# DasAltimeter_V0_41.net
KiCad netlist of a schematic drawn in EAGLE
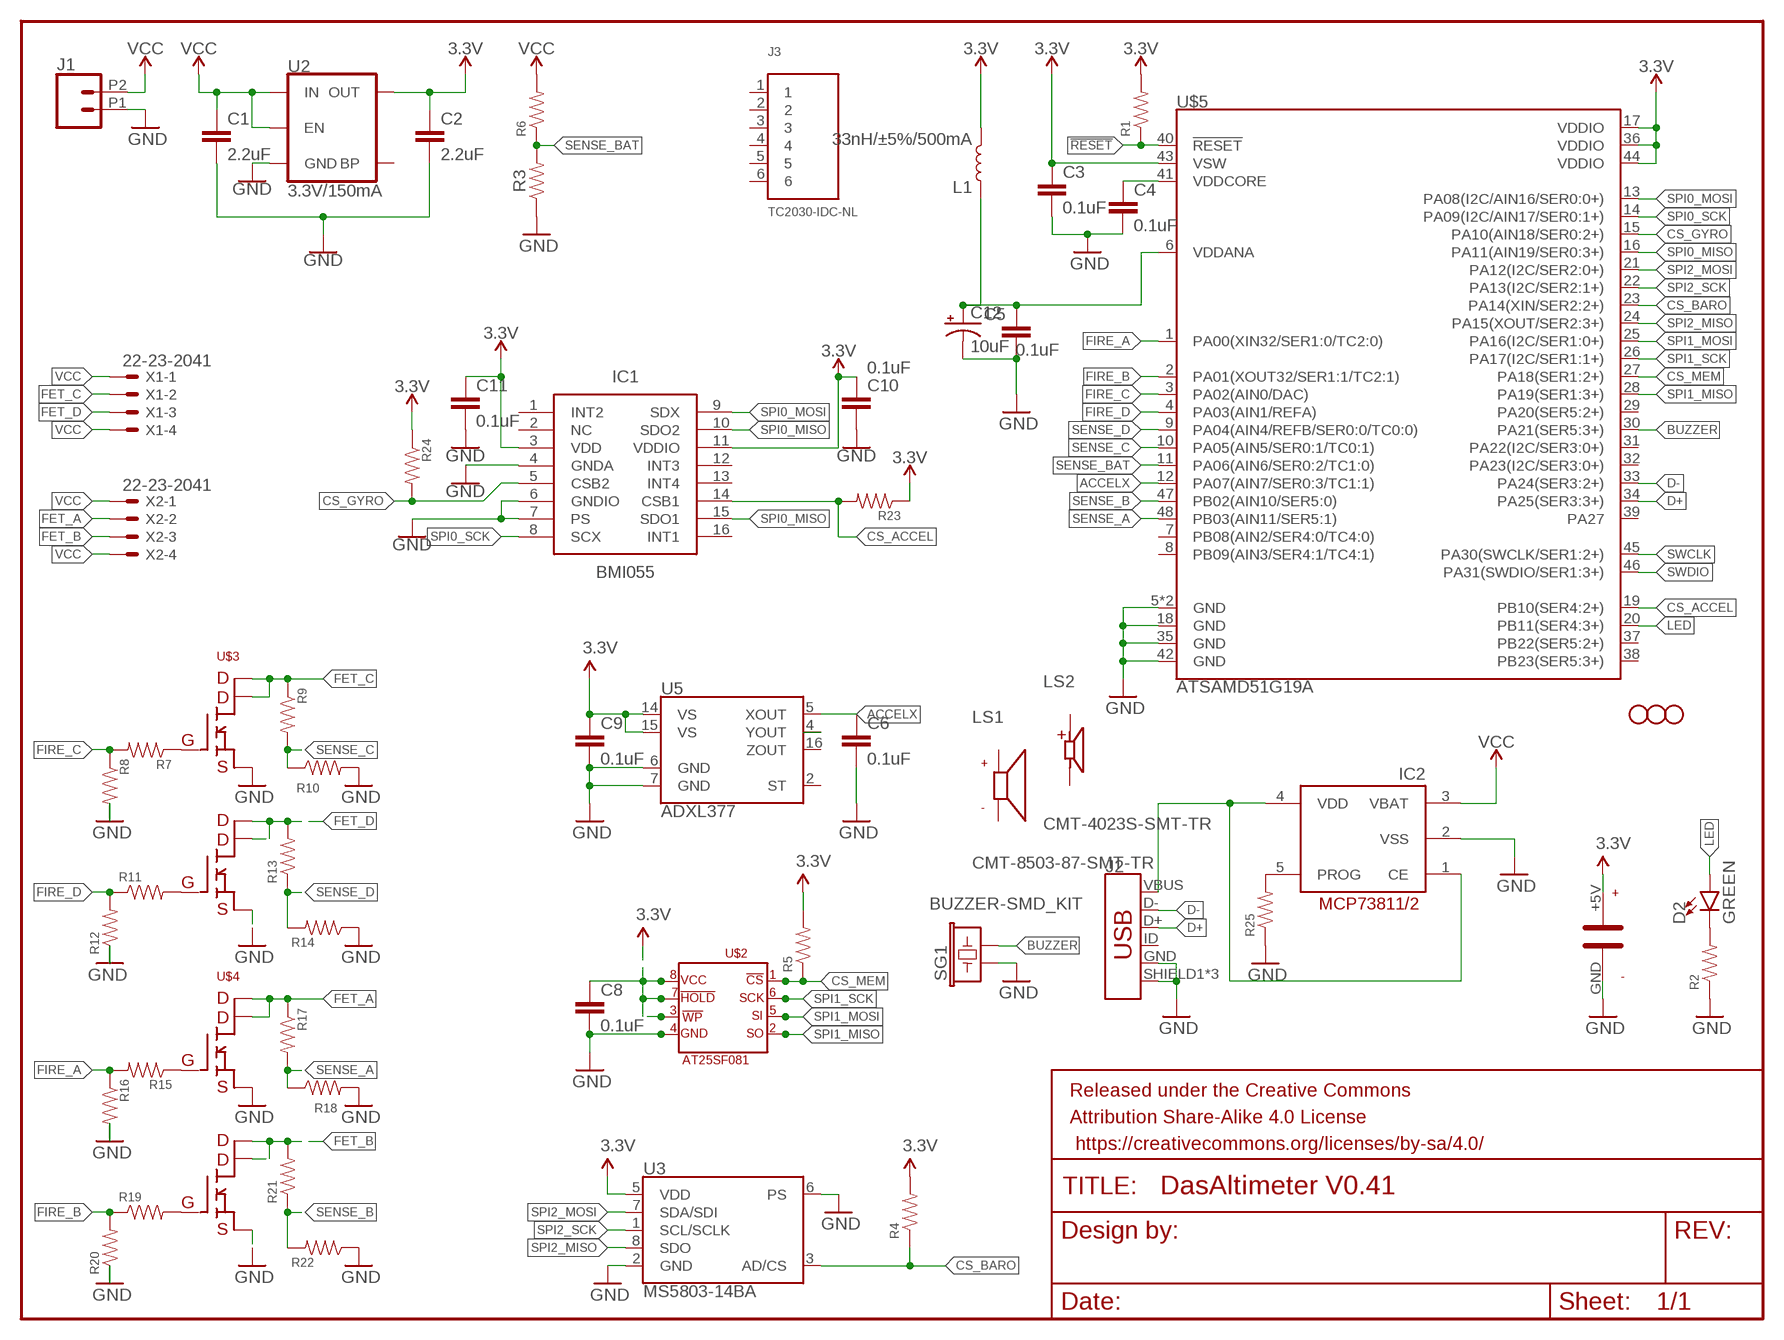
[diagram p0: schematic, sheet 1]

(export (version "E")
  (design (tool "Eeschema 10.0.6"))
  (components
    (comp (ref "C1")
      (value "2.2uF")
      (footprint "eagle-import:0603")
      (libsource (lib "eagle-import") (part "2.2UF-0603-10V-20%"))
    )
    (comp (ref "C2")
      (value "2.2uF")
      (footprint "eagle-import:0603")
      (libsource (lib "eagle-import") (part "2.2UF-0603-10V-20%"))
    )
    (comp (ref "C3")
      (value "0.1uF")
      (footprint "eagle-import:0402")
      (libsource (lib "eagle-import") (part "0.1UF-0402-16V-10%"))
    )
    (comp (ref "C4")
      (value "0.1uF")
      (footprint "eagle-import:0402")
      (libsource (lib "eagle-import") (part "0.1UF-0402-16V-10%"))
    )
    (comp (ref "C5")
      (value "0.1uF")
      (footprint "eagle-import:0402")
      (libsource (lib "eagle-import") (part "0.1UF-0402-16V-10%"))
    )
    (comp (ref "C6")
      (value "0.1uF")
      (footprint "eagle-import:0402")
      (libsource (lib "eagle-import") (part "0.1UF-0402-16V-10%"))
    )
    (comp (ref "C8")
      (value "0.1uF")
      (footprint "eagle-import:0402")
      (libsource (lib "eagle-import") (part "0.1UF-0402-16V-10%"))
    )
    (comp (ref "C9")
      (value "0.1uF")
      (footprint "eagle-import:0402")
      (libsource (lib "eagle-import") (part "0.1UF-0402-16V-10%"))
    )
    (comp (ref "C10")
      (value "0.1uF")
      (footprint "eagle-import:0402")
      (libsource (lib "eagle-import") (part "0.1UF-0402-16V-10%"))
    )
    (comp (ref "C11")
      (value "0.1uF")
      (footprint "eagle-import:0402")
      (libsource (lib "eagle-import") (part "0.1UF-0402-16V-10%"))
    )
    (comp (ref "C12")
      (value "10uF")
      (footprint "eagle-import:0603-POLAR")
      (libsource (lib "eagle-import") (part "10UF-POLAR-0603-6.3V-20%(TANT)"))
    )
    (comp (ref "D2")
      (value "GREEN")
      (footprint "eagle-import:LED-1206")
      (libsource (lib "eagle-import") (part "LED-GREEN1206"))
    )
    (comp (ref "FRAME1")
      (value "FRAME-LETTERNO_PACKAGE")
      (footprint "eagle-import:DUMMY")
      (fields (field (name "DESIGNER") "Nobody"))
      (libsource (lib "eagle-import") (part "FRAME-LETTERNO_PACKAGE"))
    )
    (comp (ref "H1")
      (value "STAND-OFFTIGHT")
      (footprint "eagle-import:STAND-OFF-TIGHT")
      (libsource (lib "eagle-import") (part "STAND-OFFTIGHT"))
    )
    (comp (ref "H2")
      (value "STAND-OFFTIGHT")
      (footprint "eagle-import:STAND-OFF-TIGHT")
      (libsource (lib "eagle-import") (part "STAND-OFFTIGHT"))
    )
    (comp (ref "H3")
      (value "STAND-OFFTIGHT")
      (footprint "eagle-import:STAND-OFF-TIGHT")
      (libsource (lib "eagle-import") (part "STAND-OFFTIGHT"))
    )
    (comp (ref "IC1")
      (value "BMI055")
      (footprint "eagle-import:BMI055")
      (libsource (lib "eagle-import") (part "BMI055"))
    )
    (comp (ref "IC2")
      (value "MCP73811/2")
      (footprint "eagle-import:SOT23-5L")
      (libsource (lib "eagle-import") (part "MCP73811/2"))
    )
    (comp (ref "J1")
      (value "CONN_022.54MM_SCREWTERM")
      (footprint "eagle-import:1X02_2.54_SCREWTERM")
      (libsource (lib "eagle-import") (part "CONN_022.54MM_SCREWTERM"))
    )
    (comp (ref "J2")
      (value "USB_MICRO-BREDUCED_PASTE")
      (footprint "eagle-import:USB-B-MICRO-SMD_RED_PASTE")
      (libsource (lib "eagle-import") (part "USB_MICRO-BREDUCED_PASTE"))
    )
    (comp (ref "J3")
      (value "TC2030-IDC-NL")
      (footprint "eagle-import:TAG_TC2030-IDC-NL")
      (fields (field (name "MF") "Tag-Connect"))
      (libsource (lib "eagle-import") (part "TC2030-IDC-NL"))
    )
    (comp (ref "L1")
      (value "33nH/±5%/500mA")
      (footprint "eagle-import:0603")
      (libsource (lib "eagle-import") (part "INDUCTOR-0603-33NH"))
    )
    (comp (ref "LS1")
      (value "CMT-8503-87-SMT-TR")
      (footprint "eagle-import:XDCR_CMT-8503-87-SMT-TR")
      (fields (field (name "MANUFACTURER") "CUI Inc."))
      (libsource (lib "eagle-import") (part "CMT-8503-87-SMT-TR"))
    )
    (comp (ref "LS2")
      (value "CMT-4023S-SMT-TR")
      (footprint "eagle-import:CUI_CMT-4023S-SMT-TR")
      (fields (field (name "MANUFACTURER") "CUI INC"))
      (libsource (lib "eagle-import") (part "CMT-4023S-SMT-TR"))
    )
    (comp (ref "R1")
      (value "RESISTOR0402")
      (footprint "eagle-import:0402")
      (libsource (lib "eagle-import") (part "RESISTOR0402"))
    )
    (comp (ref "R2")
      (value "RESISTOR0402")
      (footprint "eagle-import:0402")
      (libsource (lib "eagle-import") (part "RESISTOR0402"))
    )
    (comp (ref "R3")
      (value "RESISTOR0402")
      (footprint "eagle-import:0402")
      (libsource (lib "eagle-import") (part "RESISTOR0402"))
    )
    (comp (ref "R4")
      (value "RESISTOR0402")
      (footprint "eagle-import:0402")
      (libsource (lib "eagle-import") (part "RESISTOR0402"))
    )
    (comp (ref "R5")
      (value "RESISTOR0402")
      (footprint "eagle-import:0402")
      (libsource (lib "eagle-import") (part "RESISTOR0402"))
    )
    (comp (ref "R6")
      (value "RESISTOR0402")
      (footprint "eagle-import:0402")
      (libsource (lib "eagle-import") (part "RESISTOR0402"))
    )
    (comp (ref "R7")
      (value "RESISTOR0402")
      (footprint "eagle-import:0402")
      (libsource (lib "eagle-import") (part "RESISTOR0402"))
    )
    (comp (ref "R8")
      (value "RESISTOR0402")
      (footprint "eagle-import:0402")
      (libsource (lib "eagle-import") (part "RESISTOR0402"))
    )
    (comp (ref "R9")
      (value "RESISTOR0402")
      (footprint "eagle-import:0402")
      (libsource (lib "eagle-import") (part "RESISTOR0402"))
    )
    (comp (ref "R10")
      (value "RESISTOR0402")
      (footprint "eagle-import:0402")
      (libsource (lib "eagle-import") (part "RESISTOR0402"))
    )
    (comp (ref "R11")
      (value "RESISTOR0402")
      (footprint "eagle-import:0402")
      (libsource (lib "eagle-import") (part "RESISTOR0402"))
    )
    (comp (ref "R12")
      (value "RESISTOR0402")
      (footprint "eagle-import:0402")
      (libsource (lib "eagle-import") (part "RESISTOR0402"))
    )
    (comp (ref "R13")
      (value "RESISTOR0402")
      (footprint "eagle-import:0402")
      (libsource (lib "eagle-import") (part "RESISTOR0402"))
    )
    (comp (ref "R14")
      (value "RESISTOR0402")
      (footprint "eagle-import:0402")
      (libsource (lib "eagle-import") (part "RESISTOR0402"))
    )
    (comp (ref "R15")
      (value "RESISTOR0402")
      (footprint "eagle-import:0402")
      (libsource (lib "eagle-import") (part "RESISTOR0402"))
    )
    (comp (ref "R16")
      (value "RESISTOR0402")
      (footprint "eagle-import:0402")
      (libsource (lib "eagle-import") (part "RESISTOR0402"))
    )
    (comp (ref "R17")
      (value "RESISTOR0402")
      (footprint "eagle-import:0402")
      (libsource (lib "eagle-import") (part "RESISTOR0402"))
    )
    (comp (ref "R18")
      (value "RESISTOR0402")
      (footprint "eagle-import:0402")
      (libsource (lib "eagle-import") (part "RESISTOR0402"))
    )
    (comp (ref "R19")
      (value "RESISTOR0402")
      (footprint "eagle-import:0402")
      (libsource (lib "eagle-import") (part "RESISTOR0402"))
    )
    (comp (ref "R20")
      (value "RESISTOR0402")
      (footprint "eagle-import:0402")
      (libsource (lib "eagle-import") (part "RESISTOR0402"))
    )
    (comp (ref "R21")
      (value "RESISTOR0402")
      (footprint "eagle-import:0402")
      (libsource (lib "eagle-import") (part "RESISTOR0402"))
    )
    (comp (ref "R22")
      (value "RESISTOR0402")
      (footprint "eagle-import:0402")
      (libsource (lib "eagle-import") (part "RESISTOR0402"))
    )
    (comp (ref "R23")
      (value "RESISTOR0402")
      (footprint "eagle-import:0402")
      (libsource (lib "eagle-import") (part "RESISTOR0402"))
    )
    (comp (ref "R24")
      (value "RESISTOR0402")
      (footprint "eagle-import:0402")
      (libsource (lib "eagle-import") (part "RESISTOR0402"))
    )
    (comp (ref "R25")
      (value "RESISTOR0402")
      (footprint "eagle-import:0402")
      (libsource (lib "eagle-import") (part "RESISTOR0402"))
    )
    (comp (ref "SG1")
      (value "BUZZER-SMD_KIT")
      (footprint "eagle-import:BUZZER-CCV-KIT")
      (libsource (lib "eagle-import") (part "BUZZER-SMD_KIT"))
    )
    (comp (ref "U$1")
      (value "PB-5R0H104-R")
      (footprint "eagle-import:PB-5R0H104-R")
      (libsource (lib "eagle-import") (part "PB-5R0H104-R"))
    )
    (comp (ref "U$2")
      (value "AT25SF081")
      (footprint "eagle-import:AT25SF081")
      (libsource (lib "eagle-import") (part "AT25SF081"))
    )
    (comp (ref "U$3")
      (value "SI7232DN")
      (footprint "eagle-import:SI7232DN")
      (libsource (lib "eagle-import") (part "SI7232DN"))
    )
    (comp (ref "U$4")
      (value "SI7232DN")
      (footprint "eagle-import:SI7232DN")
      (libsource (lib "eagle-import") (part "SI7232DN"))
    )
    (comp (ref "U$5")
      (value "ATSAMD51G19A")
      (footprint "eagle-import:QFN-48")
      (libsource (lib "eagle-import") (part "ATSAMD51G19A"))
    )
    (comp (ref "U2")
      (value "3.3V/150mA")
      (footprint "eagle-import:SOT23-5")
      (libsource (lib "eagle-import") (part "V_REG_MIC52053.3V"))
    )
    (comp (ref "U3")
      (value "MS5803-14BA")
      (footprint "eagle-import:MS5803")
      (libsource (lib "eagle-import") (part "MS5803-14BA"))
    )
    (comp (ref "U5")
      (value "ADXL377")
      (footprint "eagle-import:LFCSP-16-3X3")
      (libsource (lib "eagle-import") (part "ADXL377"))
    )
    (comp (ref "X1")
      (value "22-23-2041")
      (footprint "eagle-import:22-23-2041")
      (fields (field (name "MF") "MOLEX"))
      (libsource (lib "eagle-import") (part "22-23-2041"))
    )
    (comp (ref "X2")
      (value "22-23-2041")
      (footprint "eagle-import:22-23-2041")
      (fields (field (name "MF") "MOLEX"))
      (libsource (lib "eagle-import") (part "22-23-2041"))
    )
  )
  (nets
    (net (code "1") (name "/~{RESET}") (class "Default")
      (node (ref "R1") (pin "1") (pinfunction "1_1") (pintype "passive"))
      (node (ref "U$5") (pin "40") (pinfunction "~{RESET}_40") (pintype "bidirectional"))
    )
    (net (code "2") (name "3.3V") (class "Default")
      (node (ref "C10") (pin "1") (pinfunction "1_1") (pintype "passive"))
      (node (ref "C11") (pin "1") (pinfunction "1_1") (pintype "passive"))
      (node (ref "C2") (pin "1") (pinfunction "1_1") (pintype "passive"))
      (node (ref "C3") (pin "1") (pinfunction "1_1") (pintype "passive"))
      (node (ref "C8") (pin "1") (pinfunction "1_1") (pintype "passive"))
      (node (ref "C9") (pin "1") (pinfunction "1_1") (pintype "passive"))
      (node (ref "IC1") (pin "11") (pinfunction "VDDIO_11") (pintype "passive"))
      (node (ref "IC1") (pin "3") (pinfunction "VDD_3") (pintype "passive"))
      (node (ref "L1") (pin "2") (pinfunction "2_2") (pintype "passive"))
      (node (ref "R1") (pin "2") (pinfunction "2_2") (pintype "passive"))
      (node (ref "R23") (pin "1") (pinfunction "1_1") (pintype "passive"))
      (node (ref "R24") (pin "1") (pinfunction "1_1") (pintype "passive"))
      (node (ref "R4") (pin "2") (pinfunction "2_2") (pintype "passive"))
      (node (ref "R5") (pin "2") (pinfunction "2_2") (pintype "passive"))
      (node (ref "U$1") (pin "+5V") (pinfunction "+5V_+5V") (pintype "bidirectional"))
      (node (ref "U$2") (pin "!HOLD") (pinfunction "~{HOLD}_!HOLD") (pintype "bidirectional"))
      (node (ref "U$2") (pin "!WP") (pinfunction "~{WP}_!WP") (pintype "bidirectional"))
      (node (ref "U$2") (pin "VCC") (pinfunction "VCC_VCC") (pintype "bidirectional"))
      (node (ref "U$5") (pin "17") (pinfunction "VDDIO_17") (pintype "bidirectional"))
      (node (ref "U$5") (pin "36") (pinfunction "VDDIO_36") (pintype "bidirectional"))
      (node (ref "U$5") (pin "43") (pinfunction "VSW_43") (pintype "bidirectional"))
      (node (ref "U$5") (pin "44") (pinfunction "VDDIO_44") (pintype "bidirectional"))
      (node (ref "U2") (pin "5") (pinfunction "OUT_5") (pintype "passive"))
      (node (ref "U3") (pin "5") (pinfunction "VDD_5") (pintype "bidirectional"))
      (node (ref "U5") (pin "14") (pinfunction "VS_14") (pintype "bidirectional"))
      (node (ref "U5") (pin "15") (pinfunction "VS_15") (pintype "bidirectional"))
    )
    (net (code "3") (name "ACCELX") (class "Default")
      (node (ref "C6") (pin "1") (pinfunction "1_1") (pintype "passive"))
      (node (ref "U$5") (pin "12") (pinfunction "PA07(AIN7/SER0:3/TC1:1)_12") (pintype "bidirectional"))
      (node (ref "U5") (pin "5") (pinfunction "XOUT_5") (pintype "bidirectional"))
    )
    (net (code "4") (name "BUZZER") (class "Default")
      (node (ref "SG1") (pin "-") (pinfunction "2_-") (pintype "passive"))
      (node (ref "U$5") (pin "30") (pinfunction "PA21(SER5:3+)_30") (pintype "bidirectional"))
    )
    (net (code "5") (name "CS_ACCEL") (class "Default")
      (node (ref "IC1") (pin "14") (pinfunction "CSB1_14") (pintype "passive"))
      (node (ref "R23") (pin "2") (pinfunction "2_2") (pintype "passive"))
      (node (ref "U$5") (pin "19") (pinfunction "PB10(SER4:2+)_19") (pintype "bidirectional"))
    )
    (net (code "6") (name "CS_BARO") (class "Default")
      (node (ref "R4") (pin "1") (pinfunction "1_1") (pintype "passive"))
      (node (ref "U$5") (pin "23") (pinfunction "PA14(XIN/SER2:2+)_23") (pintype "bidirectional"))
      (node (ref "U3") (pin "3") (pinfunction "AD/CS_3") (pintype "bidirectional"))
    )
    (net (code "7") (name "CS_GYRO") (class "Default")
      (node (ref "IC1") (pin "5") (pinfunction "CSB2_5") (pintype "passive"))
      (node (ref "R24") (pin "2") (pinfunction "2_2") (pintype "passive"))
      (node (ref "U$5") (pin "15") (pinfunction "PA10(AIN18/SER0:2+)_15") (pintype "bidirectional"))
    )
    (net (code "8") (name "CS_MEM") (class "Default")
      (node (ref "R5") (pin "1") (pinfunction "1_1") (pintype "passive"))
      (node (ref "U$2") (pin "!CS") (pinfunction "~{CS}_!CS") (pintype "bidirectional"))
      (node (ref "U$5") (pin "27") (pinfunction "PA18(SER1:2+)_27") (pintype "bidirectional"))
    )
    (net (code "9") (name "D+") (class "Default")
      (node (ref "J2") (pin "D+") (pinfunction "D+_D+") (pintype "bidirectional"))
      (node (ref "U$5") (pin "34") (pinfunction "PA25(SER3:3+)_34") (pintype "bidirectional"))
    )
    (net (code "10") (name "D-") (class "Default")
      (node (ref "J2") (pin "D-") (pinfunction "D-_D-") (pintype "bidirectional"))
      (node (ref "U$5") (pin "33") (pinfunction "PA24(SER3:2+)_33") (pintype "bidirectional"))
    )
    (net (code "11") (name "FET_A") (class "Default")
      (node (ref "R17") (pin "1") (pinfunction "1_1") (pintype "passive"))
      (node (ref "U$4") (pin "7") (pinfunction "PIN7_7") (pintype "bidirectional"))
      (node (ref "U$4") (pin "8") (pinfunction "PIN8_8") (pintype "bidirectional"))
      (node (ref "U$4") (pin "9") (pinfunction "PIN8_9") (pintype "bidirectional"))
      (node (ref "X2") (pin "2") (pinfunction "S_2") (pintype "passive"))
    )
    (net (code "12") (name "FET_B") (class "Default")
      (node (ref "R21") (pin "2") (pinfunction "2_2") (pintype "passive"))
      (node (ref "U$4") (pin "10") (pinfunction "PIN5_10") (pintype "bidirectional"))
      (node (ref "U$4") (pin "5") (pinfunction "PIN5_5") (pintype "bidirectional"))
      (node (ref "U$4") (pin "6") (pinfunction "PIN6_6") (pintype "bidirectional"))
      (node (ref "X2") (pin "3") (pinfunction "S_3") (pintype "passive"))
    )
    (net (code "13") (name "FET_C") (class "Default")
      (node (ref "R9") (pin "1") (pinfunction "1_1") (pintype "passive"))
      (node (ref "U$3") (pin "7") (pinfunction "PIN7_7") (pintype "bidirectional"))
      (node (ref "U$3") (pin "8") (pinfunction "PIN8_8") (pintype "bidirectional"))
      (node (ref "U$3") (pin "9") (pinfunction "PIN8_9") (pintype "bidirectional"))
      (node (ref "X1") (pin "2") (pinfunction "S_2") (pintype "passive"))
    )
    (net (code "14") (name "FET_D") (class "Default")
      (node (ref "R13") (pin "2") (pinfunction "2_2") (pintype "passive"))
      (node (ref "U$3") (pin "10") (pinfunction "PIN5_10") (pintype "bidirectional"))
      (node (ref "U$3") (pin "5") (pinfunction "PIN5_5") (pintype "bidirectional"))
      (node (ref "U$3") (pin "6") (pinfunction "PIN6_6") (pintype "bidirectional"))
      (node (ref "X1") (pin "3") (pinfunction "S_3") (pintype "passive"))
    )
    (net (code "15") (name "FIRE_A") (class "Default")
      (node (ref "R15") (pin "2") (pinfunction "2_2") (pintype "passive"))
      (node (ref "R16") (pin "1") (pinfunction "1_1") (pintype "passive"))
      (node (ref "U$5") (pin "1") (pinfunction "PA00(XIN32/SER1:0/TC2:0)_1") (pintype "bidirectional"))
    )
    (net (code "16") (name "FIRE_B") (class "Default")
      (node (ref "R19") (pin "1") (pinfunction "1_1") (pintype "passive"))
      (node (ref "R20") (pin "2") (pinfunction "2_2") (pintype "passive"))
      (node (ref "U$5") (pin "2") (pinfunction "PA01(XOUT32/SER1:1/TC2:1)_2") (pintype "bidirectional"))
    )
    (net (code "17") (name "FIRE_C") (class "Default")
      (node (ref "R7") (pin "2") (pinfunction "2_2") (pintype "passive"))
      (node (ref "R8") (pin "1") (pinfunction "1_1") (pintype "passive"))
      (node (ref "U$5") (pin "3") (pinfunction "PA02(AIN0/DAC)_3") (pintype "bidirectional"))
    )
    (net (code "18") (name "FIRE_D") (class "Default")
      (node (ref "R11") (pin "1") (pinfunction "1_1") (pintype "passive"))
      (node (ref "R12") (pin "2") (pinfunction "2_2") (pintype "passive"))
      (node (ref "U$5") (pin "4") (pinfunction "PA03(AIN1/REFA)_4") (pintype "bidirectional"))
    )
    (net (code "19") (name "GND") (class "Default")
      (node (ref "C1") (pin "2") (pinfunction "2_2") (pintype "passive"))
      (node (ref "C10") (pin "2") (pinfunction "2_2") (pintype "passive"))
      (node (ref "C11") (pin "2") (pinfunction "2_2") (pintype "passive"))
      (node (ref "C12") (pin "-") (pinfunction "-_-") (pintype "passive"))
      (node (ref "C2") (pin "2") (pinfunction "2_2") (pintype "passive"))
      (node (ref "C3") (pin "2") (pinfunction "2_2") (pintype "passive"))
      (node (ref "C4") (pin "2") (pinfunction "2_2") (pintype "passive"))
      (node (ref "C5") (pin "2") (pinfunction "2_2") (pintype "passive"))
      (node (ref "C6") (pin "2") (pinfunction "2_2") (pintype "passive"))
      (node (ref "C8") (pin "2") (pinfunction "2_2") (pintype "passive"))
      (node (ref "C9") (pin "2") (pinfunction "2_2") (pintype "passive"))
      (node (ref "IC1") (pin "4") (pinfunction "GNDA_4") (pintype "passive"))
      (node (ref "IC1") (pin "6") (pinfunction "GNDIO_6") (pintype "passive"))
      (node (ref "IC1") (pin "7") (pinfunction "PS_7") (pintype "passive"))
      (node (ref "IC2") (pin "2") (pinfunction "VSS_2") (pintype "power_in"))
      (node (ref "J1") (pin "P1") (pinfunction "1_P1") (pintype "passive"))
      (node (ref "J2") (pin "GND") (pinfunction "GND_GND") (pintype "power_in"))
      (node (ref "J2") (pin "SHIELD1") (pinfunction "SHIELD_SHIELD1") (pintype "bidirectional"))
      (node (ref "J2") (pin "SHIELD2") (pinfunction "SHIELD_SHIELD2") (pintype "bidirectional"))
      (node (ref "J2") (pin "SHIELD3") (pinfunction "SHIELD_SHIELD3") (pintype "bidirectional"))
      (node (ref "R10") (pin "2") (pinfunction "2_2") (pintype "passive"))
      (node (ref "R12") (pin "1") (pinfunction "1_1") (pintype "passive"))
      (node (ref "R14") (pin "1") (pinfunction "1_1") (pintype "passive"))
      (node (ref "R16") (pin "2") (pinfunction "2_2") (pintype "passive"))
      (node (ref "R18") (pin "2") (pinfunction "2_2") (pintype "passive"))
      (node (ref "R2") (pin "1") (pinfunction "1_1") (pintype "passive"))
      (node (ref "R20") (pin "1") (pinfunction "1_1") (pintype "passive"))
      (node (ref "R22") (pin "1") (pinfunction "1_1") (pintype "passive"))
      (node (ref "R25") (pin "1") (pinfunction "1_1") (pintype "passive"))
      (node (ref "R3") (pin "1") (pinfunction "1_1") (pintype "passive"))
      (node (ref "R8") (pin "2") (pinfunction "2_2") (pintype "passive"))
      (node (ref "SG1") (pin "+") (pinfunction "1_+") (pintype "passive"))
      (node (ref "U$1") (pin "GND") (pinfunction "GND_GND") (pintype "bidirectional"))
      (node (ref "U$2") (pin "GND") (pinfunction "GND_GND") (pintype "bidirectional"))
      (node (ref "U$3") (pin "1") (pinfunction "PIN1_1") (pintype "bidirectional"))
      (node (ref "U$3") (pin "3") (pinfunction "PIN3_3") (pintype "bidirectional"))
      (node (ref "U$4") (pin "1") (pinfunction "PIN1_1") (pintype "bidirectional"))
      (node (ref "U$4") (pin "3") (pinfunction "PIN3_3") (pintype "bidirectional"))
      (node (ref "U$5") (pin "18") (pinfunction "GND_18") (pintype "bidirectional"))
      (node (ref "U$5") (pin "35") (pinfunction "GND_35") (pintype "bidirectional"))
      (node (ref "U$5") (pin "42") (pinfunction "GND_42") (pintype "bidirectional"))
      (node (ref "U$5") (pin "5") (pinfunction "GND_5") (pintype "bidirectional"))
      (node (ref "U$5") (pin "EP") (pinfunction "GND_EP") (pintype "bidirectional"))
      (node (ref "U2") (pin "2") (pinfunction "GND_2") (pintype "input"))
      (node (ref "U3") (pin "2") (pinfunction "GND_2") (pintype "bidirectional"))
      (node (ref "U3") (pin "6") (pinfunction "PS_6") (pintype "bidirectional"))
      (node (ref "U5") (pin "6") (pinfunction "GND_6") (pintype "bidirectional"))
      (node (ref "U5") (pin "7") (pinfunction "GND_7") (pintype "bidirectional"))
    )
    (net (code "20") (name "LED") (class "Default")
      (node (ref "D2") (pin "A") (pinfunction "A_A") (pintype "passive"))
      (node (ref "U$5") (pin "20") (pinfunction "PB11(SER4:3+)_20") (pintype "bidirectional"))
    )
    (net (code "21") (name "Net-(D2-PadC)") (class "Default")
      (node (ref "D2") (pin "C") (pinfunction "C_C") (pintype "passive"))
      (node (ref "R2") (pin "2") (pinfunction "2_2") (pintype "passive"))
    )
    (net (code "22") (name "Net-(IC2-CE)") (class "Default")
      (node (ref "IC2") (pin "1") (pinfunction "CE_1") (pintype "input"))
      (node (ref "IC2") (pin "4") (pinfunction "VDD_4") (pintype "power_in"))
      (node (ref "J2") (pin "VBUS") (pinfunction "VBUS_VBUS") (pintype "power_in"))
    )
    (net (code "23") (name "Net-(IC2-PROG)") (class "Default")
      (node (ref "IC2") (pin "5") (pinfunction "PROG_5") (pintype "input"))
      (node (ref "R25") (pin "2") (pinfunction "2_2") (pintype "passive"))
    )
    (net (code "24") (name "Net-(U$3-PIN2)") (class "Default")
      (node (ref "R7") (pin "1") (pinfunction "1_1") (pintype "passive"))
      (node (ref "U$3") (pin "2") (pinfunction "PIN2_2") (pintype "bidirectional"))
    )
    (net (code "25") (name "Net-(U$3-PIN4)") (class "Default")
      (node (ref "R11") (pin "2") (pinfunction "2_2") (pintype "passive"))
      (node (ref "U$3") (pin "4") (pinfunction "PIN4_4") (pintype "bidirectional"))
    )
    (net (code "26") (name "Net-(U$4-PIN2)") (class "Default")
      (node (ref "R15") (pin "1") (pinfunction "1_1") (pintype "passive"))
      (node (ref "U$4") (pin "2") (pinfunction "PIN2_2") (pintype "bidirectional"))
    )
    (net (code "27") (name "Net-(U$4-PIN4)") (class "Default")
      (node (ref "R19") (pin "2") (pinfunction "2_2") (pintype "passive"))
      (node (ref "U$4") (pin "4") (pinfunction "PIN4_4") (pintype "bidirectional"))
    )
    (net (code "28") (name "Net-(U$5-VDDANA)") (class "Default")
      (node (ref "C12") (pin "+") (pinfunction "+_+") (pintype "passive"))
      (node (ref "C5") (pin "1") (pinfunction "1_1") (pintype "passive"))
      (node (ref "L1") (pin "1") (pinfunction "1_1") (pintype "passive"))
      (node (ref "U$5") (pin "6") (pinfunction "VDDANA_6") (pintype "bidirectional"))
    )
    (net (code "29") (name "Net-(U$5-VDDCORE)") (class "Default")
      (node (ref "C4") (pin "1") (pinfunction "1_1") (pintype "passive"))
      (node (ref "U$5") (pin "41") (pinfunction "VDDCORE_41") (pintype "bidirectional"))
    )
    (net (code "30") (name "SENSE_A") (class "Default")
      (node (ref "R17") (pin "2") (pinfunction "2_2") (pintype "passive"))
      (node (ref "R18") (pin "1") (pinfunction "1_1") (pintype "passive"))
      (node (ref "U$5") (pin "48") (pinfunction "PB03(AIN11/SER5:1)_48") (pintype "bidirectional"))
    )
    (net (code "31") (name "SENSE_B") (class "Default")
      (node (ref "R21") (pin "1") (pinfunction "1_1") (pintype "passive"))
      (node (ref "R22") (pin "2") (pinfunction "2_2") (pintype "passive"))
      (node (ref "U$5") (pin "47") (pinfunction "PB02(AIN10/SER5:0)_47") (pintype "bidirectional"))
    )
    (net (code "32") (name "SENSE_BAT") (class "Default")
      (node (ref "R3") (pin "2") (pinfunction "2_2") (pintype "passive"))
      (node (ref "R6") (pin "1") (pinfunction "1_1") (pintype "passive"))
      (node (ref "U$5") (pin "11") (pinfunction "PA06(AIN6/SER0:2/TC1:0)_11") (pintype "bidirectional"))
    )
    (net (code "33") (name "SENSE_C") (class "Default")
      (node (ref "R10") (pin "1") (pinfunction "1_1") (pintype "passive"))
      (node (ref "R9") (pin "2") (pinfunction "2_2") (pintype "passive"))
      (node (ref "U$5") (pin "10") (pinfunction "PA05(AIN5/SER0:1/TC0:1)_10") (pintype "bidirectional"))
    )
    (net (code "34") (name "SENSE_D") (class "Default")
      (node (ref "R13") (pin "1") (pinfunction "1_1") (pintype "passive"))
      (node (ref "R14") (pin "2") (pinfunction "2_2") (pintype "passive"))
      (node (ref "U$5") (pin "9") (pinfunction "PA04(AIN4/REFB/SER0:0/TC0:0)_9") (pintype "bidirectional"))
    )
    (net (code "35") (name "SPI0_MISO") (class "Default")
      (node (ref "IC1") (pin "10") (pinfunction "SDO2_10") (pintype "passive"))
      (node (ref "IC1") (pin "15") (pinfunction "SDO1_15") (pintype "passive"))
      (node (ref "U$5") (pin "16") (pinfunction "PA11(AIN19/SER0:3+)_16") (pintype "bidirectional"))
    )
    (net (code "36") (name "SPI0_MOSI") (class "Default")
      (node (ref "IC1") (pin "9") (pinfunction "SDX_9") (pintype "passive"))
      (node (ref "U$5") (pin "13") (pinfunction "PA08(I2C/AIN16/SER0:0+)_13") (pintype "bidirectional"))
    )
    (net (code "37") (name "SPI0_SCK") (class "Default")
      (node (ref "IC1") (pin "8") (pinfunction "SCX_8") (pintype "passive"))
      (node (ref "U$5") (pin "14") (pinfunction "PA09(I2C/AIN17/SER0:1+)_14") (pintype "bidirectional"))
    )
    (net (code "38") (name "SPI1_MISO") (class "Default")
      (node (ref "U$2") (pin "SO") (pinfunction "SO_SO") (pintype "bidirectional"))
      (node (ref "U$5") (pin "28") (pinfunction "PA19(SER1:3+)_28") (pintype "bidirectional"))
    )
    (net (code "39") (name "SPI1_MOSI") (class "Default")
      (node (ref "U$2") (pin "SI") (pinfunction "SI_SI") (pintype "bidirectional"))
      (node (ref "U$5") (pin "25") (pinfunction "PA16(I2C/SER1:0+)_25") (pintype "bidirectional"))
    )
    (net (code "40") (name "SPI1_SCK") (class "Default")
      (node (ref "U$2") (pin "SCK") (pinfunction "SCK_SCK") (pintype "bidirectional"))
      (node (ref "U$5") (pin "26") (pinfunction "PA17(I2C/SER1:1+)_26") (pintype "bidirectional"))
    )
    (net (code "41") (name "SPI2_MISO") (class "Default")
      (node (ref "U$5") (pin "24") (pinfunction "PA15(XOUT/SER2:3+)_24") (pintype "bidirectional"))
      (node (ref "U3") (pin "8") (pinfunction "SDO_8") (pintype "bidirectional"))
    )
    (net (code "42") (name "SPI2_MOSI") (class "Default")
      (node (ref "U$5") (pin "21") (pinfunction "PA12(I2C/SER2:0+)_21") (pintype "bidirectional"))
      (node (ref "U3") (pin "7") (pinfunction "SDA/SDI_7") (pintype "bidirectional"))
    )
    (net (code "43") (name "SPI2_SCK") (class "Default")
      (node (ref "U$5") (pin "22") (pinfunction "PA13(I2C/SER2:1+)_22") (pintype "bidirectional"))
      (node (ref "U3") (pin "1") (pinfunction "SCL/SCLK_1") (pintype "bidirectional"))
    )
    (net (code "44") (name "SWCLK") (class "Default")
      (node (ref "U$5") (pin "45") (pinfunction "PA30(SWCLK/SER1:2+)_45") (pintype "bidirectional"))
    )
    (net (code "45") (name "SWDIO") (class "Default")
      (node (ref "U$5") (pin "46") (pinfunction "PA31(SWDIO/SER1:3+)_46") (pintype "bidirectional"))
    )
    (net (code "46") (name "VCC") (class "Default")
      (node (ref "C1") (pin "1") (pinfunction "1_1") (pintype "passive"))
      (node (ref "IC2") (pin "3") (pinfunction "VBAT_3") (pintype "bidirectional"))
      (node (ref "J1") (pin "P2") (pinfunction "2_P2") (pintype "passive"))
      (node (ref "R6") (pin "2") (pinfunction "2_2") (pintype "passive"))
      (node (ref "U2") (pin "1") (pinfunction "IN_1") (pintype "input"))
      (node (ref "U2") (pin "3") (pinfunction "EN_3") (pintype "input"))
      (node (ref "X1") (pin "1") (pinfunction "S_1") (pintype "passive"))
      (node (ref "X1") (pin "4") (pinfunction "S_4") (pintype "passive"))
      (node (ref "X2") (pin "1") (pinfunction "S_1") (pintype "passive"))
      (node (ref "X2") (pin "4") (pinfunction "S_4") (pintype "passive"))
    )
    (net (code "47") (name "unconnected-(IC1-INT1-Pad16)") (class "Default")
      (node (ref "IC1") (pin "16") (pinfunction "INT1_16") (pintype "passive"))
    )
    (net (code "48") (name "unconnected-(IC1-INT2-Pad1)") (class "Default")
      (node (ref "IC1") (pin "1") (pinfunction "INT2_1") (pintype "passive"))
    )
    (net (code "49") (name "unconnected-(IC1-INT3-Pad12)") (class "Default")
      (node (ref "IC1") (pin "12") (pinfunction "INT3_12") (pintype "passive"))
    )
    (net (code "50") (name "unconnected-(IC1-INT4-Pad13)") (class "Default")
      (node (ref "IC1") (pin "13") (pinfunction "INT4_13") (pintype "passive"))
    )
    (net (code "51") (name "unconnected-(IC1-NC-Pad2)") (class "Default")
      (node (ref "IC1") (pin "2") (pinfunction "NC_2") (pintype "no_connect"))
    )
    (net (code "52") (name "unconnected-(J2-PadID)") (class "Default")
      (node (ref "J2") (pin "ID") (pinfunction "ID_ID") (pintype "bidirectional"))
    )
    (net (code "53") (name "unconnected-(J3-Pad1)") (class "Default")
      (node (ref "J3") (pin "1") (pinfunction "1_1") (pintype "passive"))
    )
    (net (code "54") (name "unconnected-(J3-Pad2)") (class "Default")
      (node (ref "J3") (pin "2") (pinfunction "2_2") (pintype "passive"))
    )
    (net (code "55") (name "unconnected-(J3-Pad3)") (class "Default")
      (node (ref "J3") (pin "3") (pinfunction "3_3") (pintype "passive"))
    )
    (net (code "56") (name "unconnected-(J3-Pad4)") (class "Default")
      (node (ref "J3") (pin "4") (pinfunction "4_4") (pintype "passive"))
    )
    (net (code "57") (name "unconnected-(J3-Pad5)") (class "Default")
      (node (ref "J3") (pin "5") (pinfunction "5_5") (pintype "passive"))
    )
    (net (code "58") (name "unconnected-(J3-Pad6)") (class "Default")
      (node (ref "J3") (pin "6") (pinfunction "6_6") (pintype "passive"))
    )
    (net (code "59") (name "unconnected-(LS1-PadN)") (class "Default")
      (node (ref "LS1") (pin "N") (pinfunction "N_N") (pintype "passive"))
    )
    (net (code "60") (name "unconnected-(LS1-PadP)") (class "Default")
      (node (ref "LS1") (pin "P") (pinfunction "P_P") (pintype "passive"))
    )
    (net (code "61") (name "unconnected-(LS2-PadN)") (class "Default")
      (node (ref "LS2") (pin "N") (pinfunction "N_N") (pintype "passive"))
    )
    (net (code "62") (name "unconnected-(LS2-PadP)") (class "Default")
      (node (ref "LS2") (pin "P") (pinfunction "P_P") (pintype "passive"))
    )
    (net (code "63") (name "unconnected-(U$5-PA20(SER5:2+)-Pad29)") (class "Default")
      (node (ref "U$5") (pin "29") (pinfunction "PA20(SER5:2+)_29") (pintype "bidirectional"))
    )
    (net (code "64") (name "unconnected-(U$5-PA22(I2C{slash}SER3:0+)-Pad31)") (class "Default")
      (node (ref "U$5") (pin "31") (pinfunction "PA22(I2C/SER3:0+)_31") (pintype "bidirectional"))
    )
    (net (code "65") (name "unconnected-(U$5-PA23(I2C{slash}SER3:0+)-Pad32)") (class "Default")
      (node (ref "U$5") (pin "32") (pinfunction "PA23(I2C/SER3:0+)_32") (pintype "bidirectional"))
    )
    (net (code "66") (name "unconnected-(U$5-PA27-Pad39)") (class "Default")
      (node (ref "U$5") (pin "39") (pinfunction "PA27_39") (pintype "bidirectional"))
    )
    (net (code "67") (name "unconnected-(U$5-PB08(AIN2{slash}SER4:0{slash}TC4:0)-Pad7)") (class "Default")
      (node (ref "U$5") (pin "7") (pinfunction "PB08(AIN2/SER4:0/TC4:0)_7") (pintype "bidirectional"))
    )
    (net (code "68") (name "unconnected-(U$5-PB09(AIN3{slash}SER4:1{slash}TC4:1)-Pad8)") (class "Default")
      (node (ref "U$5") (pin "8") (pinfunction "PB09(AIN3/SER4:1/TC4:1)_8") (pintype "bidirectional"))
    )
    (net (code "69") (name "unconnected-(U$5-PB22(SER5:2+)-Pad37)") (class "Default")
      (node (ref "U$5") (pin "37") (pinfunction "PB22(SER5:2+)_37") (pintype "bidirectional"))
    )
    (net (code "70") (name "unconnected-(U$5-PB23(SER5:3+)-Pad38)") (class "Default")
      (node (ref "U$5") (pin "38") (pinfunction "PB23(SER5:3+)_38") (pintype "bidirectional"))
    )
    (net (code "71") (name "unconnected-(U2-BP-Pad4)") (class "Default")
      (node (ref "U2") (pin "4") (pinfunction "BP_4") (pintype "input"))
    )
    (net (code "72") (name "unconnected-(U5-ST-Pad2)") (class "Default")
      (node (ref "U5") (pin "2") (pinfunction "ST_2") (pintype "bidirectional"))
    )
    (net (code "73") (name "unconnected-(U5-YOUT-Pad4)") (class "Default")
      (node (ref "U5") (pin "4") (pinfunction "YOUT_4") (pintype "bidirectional"))
    )
    (net (code "74") (name "unconnected-(U5-ZOUT-Pad16)") (class "Default")
      (node (ref "U5") (pin "16") (pinfunction "ZOUT_16") (pintype "bidirectional"))
    )
  )
)
